# RS485.net
KiCad netlist of a schematic drawn in Altium Designer
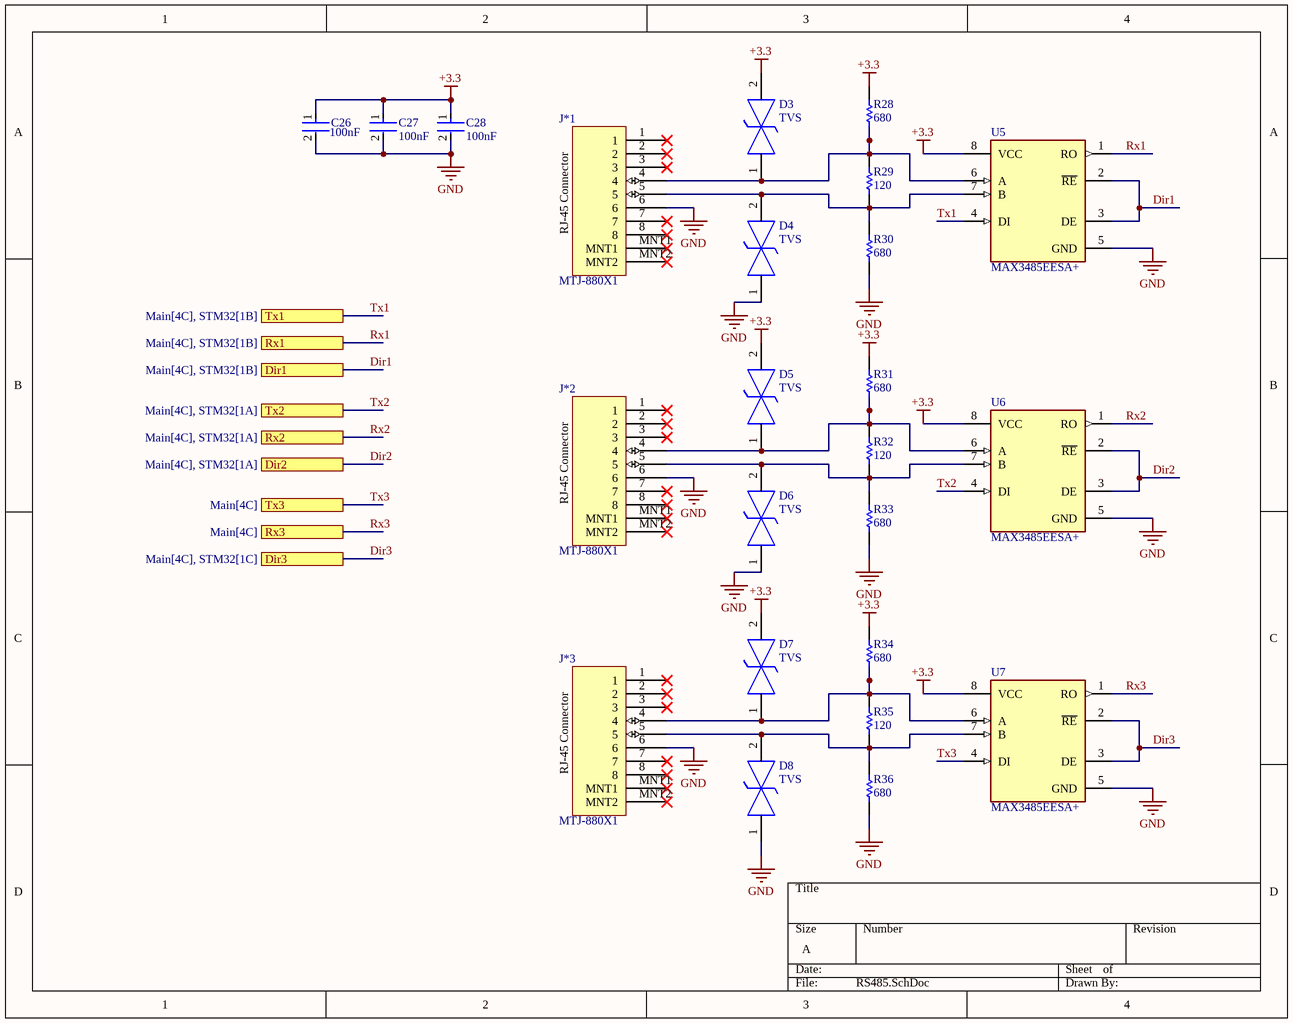
[diagram p0: RS485.SchDoc]

(export (version "E")
  (design (tool "Eeschema 10.0.6"))
  (components
    (comp (ref "C26")
      (value "100nF")
      (footprint "FP-0805-L_2_01_0_2-W_1_25-IPC_B")
      (description "General Purpose Ceramic Capacitor, 0805, 100nF, 10%, X7R, 15%, 100V")
      (fields (field (name "VOLTAGE") "100V") (field (name "TOLERANCE") "10%"))
      (libsource (lib "Altium Content Vault") (part "b4654b650e69147ec39a6b967a45e02"))
    )
    (comp (ref "C27")
      (value "100nF")
      (footprint "FP-0805-L_2_01_0_2-W_1_25-IPC_B")
      (description "General Purpose Ceramic Capacitor, 0805, 100nF, 10%, X7R, 15%, 100V")
      (fields (field (name "VOLTAGE") "100V") (field (name "TOLERANCE") "10%"))
      (libsource (lib "Altium Content Vault") (part "b4654b650e69147ec39a6b967a45e02"))
    )
    (comp (ref "C28")
      (value "100nF")
      (footprint "FP-0805-L_2_01_0_2-W_1_25-IPC_B")
      (description "General Purpose Ceramic Capacitor, 0805, 100nF, 10%, X7R, 15%, 100V")
      (fields (field (name "VOLTAGE") "100V") (field (name "TOLERANCE") "10%"))
      (libsource (lib "Altium Content Vault") (part "b4654b650e69147ec39a6b967a45e02"))
    )
    (comp (ref "D3")
      (value "TVS")
      (footprint "FP-SMB-MFG")
      (description "TVS DIODE 28.2V 59V SMB")
      (fields
        (field (name "OCTOPART") "https://octopart.com/sm6t33ca-stmicroelectronics-55399331")
        (field (name "MANUFACTURER PART NUMBER") "SM6T33CA")
      )
      (libsource (lib "Altium Content Vault") (part "ebc102d6f37e12f28676a717a4d7ff6"))
    )
    (comp (ref "D4")
      (value "TVS")
      (footprint "FP-SMB-MFG")
      (description "TVS DIODE 28.2V 59V SMB")
      (fields
        (field (name "OCTOPART") "https://octopart.com/sm6t33ca-stmicroelectronics-55399331")
        (field (name "MANUFACTURER PART NUMBER") "SM6T33CA")
      )
      (libsource (lib "Altium Content Vault") (part "ebc102d6f37e12f28676a717a4d7ff6"))
    )
    (comp (ref "D5")
      (value "TVS")
      (footprint "FP-SMB-MFG")
      (description "TVS DIODE 28.2V 59V SMB")
      (fields
        (field (name "OCTOPART") "https://octopart.com/sm6t33ca-stmicroelectronics-55399331")
        (field (name "MANUFACTURER PART NUMBER") "SM6T33CA")
      )
      (libsource (lib "Altium Content Vault") (part "ebc102d6f37e12f28676a717a4d7ff6"))
    )
    (comp (ref "D6")
      (value "TVS")
      (footprint "FP-SMB-MFG")
      (description "TVS DIODE 28.2V 59V SMB")
      (fields
        (field (name "OCTOPART") "https://octopart.com/sm6t33ca-stmicroelectronics-55399331")
        (field (name "MANUFACTURER PART NUMBER") "SM6T33CA")
      )
      (libsource (lib "Altium Content Vault") (part "ebc102d6f37e12f28676a717a4d7ff6"))
    )
    (comp (ref "D7")
      (value "TVS")
      (footprint "FP-SMB-MFG")
      (description "TVS DIODE 28.2V 59V SMB")
      (fields
        (field (name "OCTOPART") "https://octopart.com/sm6t33ca-stmicroelectronics-55399331")
        (field (name "MANUFACTURER PART NUMBER") "SM6T33CA")
      )
      (libsource (lib "Altium Content Vault") (part "ebc102d6f37e12f28676a717a4d7ff6"))
    )
    (comp (ref "D8")
      (value "TVS")
      (footprint "FP-SMB-MFG")
      (description "TVS DIODE 28.2V 59V SMB")
      (fields
        (field (name "OCTOPART") "https://octopart.com/sm6t33ca-stmicroelectronics-55399331")
        (field (name "MANUFACTURER PART NUMBER") "SM6T33CA")
      )
      (libsource (lib "Altium Content Vault") (part "ebc102d6f37e12f28676a717a4d7ff6"))
    )
    (comp (ref "J*1")
      (value "MTJ-880X1")
      (footprint "MTJ-880X1")
      (libsource (lib "Schematic_library") (part "MTJ-880X1"))
    )
    (comp (ref "J*2")
      (value "MTJ-880X1")
      (footprint "MTJ-880X1")
      (libsource (lib "Schematic_library") (part "MTJ-880X1"))
    )
    (comp (ref "J*3")
      (value "MTJ-880X1")
      (footprint "MTJ-880X1")
      (libsource (lib "Schematic_library") (part "MTJ-880X1"))
    )
    (comp (ref "R28")
      (value "680")
      (footprint "RESC2013X50X30LL20T20")
      (fields (field (name "MANUFACTURER") "Vishay Dale") (field (name "PART NUMBER") "CRCW08050000Z0EA"))
      (libsource (lib "Altium Content Vault") (part "RES"))
    )
    (comp (ref "R29")
      (value "120")
      (footprint "RESC2013X50X30LL20T20")
      (fields (field (name "MANUFACTURER") "Vishay Dale") (field (name "PART NUMBER") "CRCW08050000Z0EA"))
      (libsource (lib "Altium Content Vault") (part "RES"))
    )
    (comp (ref "R30")
      (value "680")
      (footprint "RESC2013X50X30LL20T20")
      (fields (field (name "MANUFACTURER") "Vishay Dale") (field (name "PART NUMBER") "CRCW08050000Z0EA"))
      (libsource (lib "Altium Content Vault") (part "RES"))
    )
    (comp (ref "R31")
      (value "680")
      (footprint "RESC2013X50X30LL20T20")
      (fields (field (name "MANUFACTURER") "Vishay Dale") (field (name "PART NUMBER") "CRCW08050000Z0EA"))
      (libsource (lib "Altium Content Vault") (part "RES"))
    )
    (comp (ref "R32")
      (value "120")
      (footprint "RESC2013X50X30LL20T20")
      (fields (field (name "MANUFACTURER") "Vishay Dale") (field (name "PART NUMBER") "CRCW08050000Z0EA"))
      (libsource (lib "Altium Content Vault") (part "RES"))
    )
    (comp (ref "R33")
      (value "680")
      (footprint "RESC2013X50X30LL20T20")
      (fields (field (name "MANUFACTURER") "Vishay Dale") (field (name "PART NUMBER") "CRCW08050000Z0EA"))
      (libsource (lib "Altium Content Vault") (part "RES"))
    )
    (comp (ref "R34")
      (value "680")
      (footprint "RESC2013X50X30LL20T20")
      (fields (field (name "MANUFACTURER") "Vishay Dale") (field (name "PART NUMBER") "CRCW08050000Z0EA"))
      (libsource (lib "Altium Content Vault") (part "RES"))
    )
    (comp (ref "R35")
      (value "120")
      (footprint "RESC2013X50X30LL20T20")
      (fields (field (name "MANUFACTURER") "Vishay Dale") (field (name "PART NUMBER") "CRCW08050000Z0EA"))
      (libsource (lib "Altium Content Vault") (part "RES"))
    )
    (comp (ref "R36")
      (value "680")
      (footprint "RESC2013X50X30LL20T20")
      (fields (field (name "MANUFACTURER") "Vishay Dale") (field (name "PART NUMBER") "CRCW08050000Z0EA"))
      (libsource (lib "Altium Content Vault") (part "RES"))
    )
    (comp (ref "U5")
      (value "MAX3485EESA+")
      (footprint "FP-S8-5-MFG")
      (description "IC TXRX RS485/422 10MBPS 8SOIC")
      (fields
        (field (name "OCTOPART") "https://octopart.com/max3485eesa%2B-maxim+integrated-39731903")
        (field (name "MANUFACTURER") "Maxim Integrated")
      )
      (libsource (lib "Altium Content Vault") (part "be0caabdb159a9a12bcb36ec340889e"))
    )
    (comp (ref "U6")
      (value "MAX3485EESA+")
      (footprint "FP-S8-5-MFG")
      (description "IC TXRX RS485/422 10MBPS 8SOIC")
      (fields
        (field (name "OCTOPART") "https://octopart.com/max3485eesa%2B-maxim+integrated-39731903")
        (field (name "MANUFACTURER") "Maxim Integrated")
      )
      (libsource (lib "Altium Content Vault") (part "be0caabdb159a9a12bcb36ec340889e"))
    )
    (comp (ref "U7")
      (value "MAX3485EESA+")
      (footprint "FP-S8-5-MFG")
      (description "IC TXRX RS485/422 10MBPS 8SOIC")
      (fields
        (field (name "OCTOPART") "https://octopart.com/max3485eesa%2B-maxim+integrated-39731903")
        (field (name "MANUFACTURER") "Maxim Integrated")
      )
      (libsource (lib "Altium Content Vault") (part "be0caabdb159a9a12bcb36ec340889e"))
    )
  )
  (nets
    (net (code "1") (name "+3.3") (class "Default")
      (node (ref "C26") (pin "1") (pinfunction "1_1") (pintype "passive"))
      (node (ref "C27") (pin "1") (pinfunction "1_1") (pintype "passive"))
      (node (ref "C28") (pin "1") (pinfunction "1_1") (pintype "passive"))
      (node (ref "D3") (pin "2") (pinfunction "2_2") (pintype "passive"))
      (node (ref "D5") (pin "2") (pinfunction "2_2") (pintype "passive"))
      (node (ref "D7") (pin "2") (pinfunction "2_2") (pintype "passive"))
      (node (ref "R28") (pin "2") (pinfunction "2_2") (pintype "passive"))
      (node (ref "R31") (pin "2") (pinfunction "2_2") (pintype "passive"))
      (node (ref "R34") (pin "2") (pinfunction "2_2") (pintype "passive"))
      (node (ref "U5") (pin "8") (pinfunction "VCC_8") (pintype "power_in"))
      (node (ref "U6") (pin "8") (pinfunction "VCC_8") (pintype "power_in"))
      (node (ref "U7") (pin "8") (pinfunction "VCC_8") (pintype "power_in"))
    )
    (net (code "2") (name "/Dir1") (class "Default")
      (node (ref "U5") (pin "2") (pinfunction "~{RE}_2") (pintype "passive"))
      (node (ref "U5") (pin "3") (pinfunction "DE_3") (pintype "passive"))
    )
    (net (code "3") (name "/Dir2") (class "Default")
      (node (ref "U6") (pin "2") (pinfunction "~{RE}_2") (pintype "passive"))
      (node (ref "U6") (pin "3") (pinfunction "DE_3") (pintype "passive"))
    )
    (net (code "4") (name "/Dir3") (class "Default")
      (node (ref "U7") (pin "2") (pinfunction "~{RE}_2") (pintype "passive"))
      (node (ref "U7") (pin "3") (pinfunction "DE_3") (pintype "passive"))
    )
    (net (code "5") (name "/Rx1") (class "Default")
      (node (ref "U5") (pin "1") (pinfunction "RO_1") (pintype "output"))
    )
    (net (code "6") (name "/Rx2") (class "Default")
      (node (ref "U6") (pin "1") (pinfunction "RO_1") (pintype "output"))
    )
    (net (code "7") (name "/Rx3") (class "Default")
      (node (ref "U7") (pin "1") (pinfunction "RO_1") (pintype "output"))
    )
    (net (code "8") (name "/Tx1") (class "Default")
      (node (ref "U5") (pin "4") (pinfunction "DI_4") (pintype "input"))
    )
    (net (code "9") (name "/Tx2") (class "Default")
      (node (ref "U6") (pin "4") (pinfunction "DI_4") (pintype "input"))
    )
    (net (code "10") (name "/Tx3") (class "Default")
      (node (ref "U7") (pin "4") (pinfunction "DI_4") (pintype "input"))
    )
    (net (code "11") (name "GND") (class "Default")
      (node (ref "C26") (pin "2") (pinfunction "2_2") (pintype "passive"))
      (node (ref "C27") (pin "2") (pinfunction "2_2") (pintype "passive"))
      (node (ref "C28") (pin "2") (pinfunction "2_2") (pintype "passive"))
      (node (ref "D4") (pin "1") (pinfunction "1_1") (pintype "passive"))
      (node (ref "D6") (pin "1") (pinfunction "1_1") (pintype "passive"))
      (node (ref "D8") (pin "1") (pinfunction "1_1") (pintype "passive"))
      (node (ref "J*1") (pin "6") (pinfunction "6_6") (pintype "passive"))
      (node (ref "J*2") (pin "6") (pinfunction "6_6") (pintype "passive"))
      (node (ref "J*3") (pin "6") (pinfunction "6_6") (pintype "passive"))
      (node (ref "R30") (pin "1") (pinfunction "1_1") (pintype "passive"))
      (node (ref "R33") (pin "1") (pinfunction "1_1") (pintype "passive"))
      (node (ref "R36") (pin "1") (pinfunction "1_1") (pintype "passive"))
      (node (ref "U5") (pin "5") (pinfunction "GND_5") (pintype "power_in"))
      (node (ref "U6") (pin "5") (pinfunction "GND_5") (pintype "power_in"))
      (node (ref "U7") (pin "5") (pinfunction "GND_5") (pintype "power_in"))
    )
    (net (code "12") (name "Net-(U5-A)") (class "Default")
      (node (ref "D3") (pin "1") (pinfunction "1_1") (pintype "passive"))
      (node (ref "J*1") (pin "4") (pinfunction "4_4") (pintype "bidirectional"))
      (node (ref "R28") (pin "1") (pinfunction "1_1") (pintype "passive"))
      (node (ref "R29") (pin "2") (pinfunction "2_2") (pintype "passive"))
      (node (ref "U5") (pin "6") (pinfunction "A_6") (pintype "input"))
    )
    (net (code "13") (name "Net-(U5-B)") (class "Default")
      (node (ref "D4") (pin "2") (pinfunction "2_2") (pintype "passive"))
      (node (ref "J*1") (pin "5") (pinfunction "5_5") (pintype "bidirectional"))
      (node (ref "R29") (pin "1") (pinfunction "1_1") (pintype "passive"))
      (node (ref "R30") (pin "2") (pinfunction "2_2") (pintype "passive"))
      (node (ref "U5") (pin "7") (pinfunction "B_7") (pintype "input"))
    )
    (net (code "14") (name "Net-(U6-A)") (class "Default")
      (node (ref "D5") (pin "1") (pinfunction "1_1") (pintype "passive"))
      (node (ref "J*2") (pin "4") (pinfunction "4_4") (pintype "bidirectional"))
      (node (ref "R31") (pin "1") (pinfunction "1_1") (pintype "passive"))
      (node (ref "R32") (pin "2") (pinfunction "2_2") (pintype "passive"))
      (node (ref "U6") (pin "6") (pinfunction "A_6") (pintype "input"))
    )
    (net (code "15") (name "Net-(U6-B)") (class "Default")
      (node (ref "D6") (pin "2") (pinfunction "2_2") (pintype "passive"))
      (node (ref "J*2") (pin "5") (pinfunction "5_5") (pintype "bidirectional"))
      (node (ref "R32") (pin "1") (pinfunction "1_1") (pintype "passive"))
      (node (ref "R33") (pin "2") (pinfunction "2_2") (pintype "passive"))
      (node (ref "U6") (pin "7") (pinfunction "B_7") (pintype "input"))
    )
    (net (code "16") (name "Net-(U7-A)") (class "Default")
      (node (ref "D7") (pin "1") (pinfunction "1_1") (pintype "passive"))
      (node (ref "J*3") (pin "4") (pinfunction "4_4") (pintype "bidirectional"))
      (node (ref "R34") (pin "1") (pinfunction "1_1") (pintype "passive"))
      (node (ref "R35") (pin "2") (pinfunction "2_2") (pintype "passive"))
      (node (ref "U7") (pin "6") (pinfunction "A_6") (pintype "input"))
    )
    (net (code "17") (name "Net-(U7-B)") (class "Default")
      (node (ref "D8") (pin "2") (pinfunction "2_2") (pintype "passive"))
      (node (ref "J*3") (pin "5") (pinfunction "5_5") (pintype "bidirectional"))
      (node (ref "R35") (pin "1") (pinfunction "1_1") (pintype "passive"))
      (node (ref "R36") (pin "2") (pinfunction "2_2") (pintype "passive"))
      (node (ref "U7") (pin "7") (pinfunction "B_7") (pintype "input"))
    )
    (net (code "18") (name "unconnected-(J*1-Pad1)") (class "Default")
      (node (ref "J*1") (pin "1") (pinfunction "1_1") (pintype "passive+no_connect"))
    )
    (net (code "19") (name "unconnected-(J*1-Pad2)") (class "Default")
      (node (ref "J*1") (pin "2") (pinfunction "2_2") (pintype "passive+no_connect"))
    )
    (net (code "20") (name "unconnected-(J*1-Pad3)") (class "Default")
      (node (ref "J*1") (pin "3") (pinfunction "3_3") (pintype "passive+no_connect"))
    )
    (net (code "21") (name "unconnected-(J*1-Pad7)") (class "Default")
      (node (ref "J*1") (pin "7") (pinfunction "7_7") (pintype "passive+no_connect"))
    )
    (net (code "22") (name "unconnected-(J*1-Pad8)") (class "Default")
      (node (ref "J*1") (pin "8") (pinfunction "8_8") (pintype "passive+no_connect"))
    )
    (net (code "23") (name "unconnected-(J*1-PadMNT1)") (class "Default")
      (node (ref "J*1") (pin "MNT1") (pinfunction "MNT1_MNT1") (pintype "passive+no_connect"))
    )
    (net (code "24") (name "unconnected-(J*1-PadMNT2)") (class "Default")
      (node (ref "J*1") (pin "MNT2") (pinfunction "MNT2_MNT2") (pintype "passive+no_connect"))
    )
    (net (code "25") (name "unconnected-(J*2-Pad1)") (class "Default")
      (node (ref "J*2") (pin "1") (pinfunction "1_1") (pintype "passive+no_connect"))
    )
    (net (code "26") (name "unconnected-(J*2-Pad2)") (class "Default")
      (node (ref "J*2") (pin "2") (pinfunction "2_2") (pintype "passive+no_connect"))
    )
    (net (code "27") (name "unconnected-(J*2-Pad3)") (class "Default")
      (node (ref "J*2") (pin "3") (pinfunction "3_3") (pintype "passive+no_connect"))
    )
    (net (code "28") (name "unconnected-(J*2-Pad7)") (class "Default")
      (node (ref "J*2") (pin "7") (pinfunction "7_7") (pintype "passive+no_connect"))
    )
    (net (code "29") (name "unconnected-(J*2-Pad8)") (class "Default")
      (node (ref "J*2") (pin "8") (pinfunction "8_8") (pintype "passive+no_connect"))
    )
    (net (code "30") (name "unconnected-(J*2-PadMNT1)") (class "Default")
      (node (ref "J*2") (pin "MNT1") (pinfunction "MNT1_MNT1") (pintype "passive+no_connect"))
    )
    (net (code "31") (name "unconnected-(J*2-PadMNT2)") (class "Default")
      (node (ref "J*2") (pin "MNT2") (pinfunction "MNT2_MNT2") (pintype "passive+no_connect"))
    )
    (net (code "32") (name "unconnected-(J*3-Pad1)") (class "Default")
      (node (ref "J*3") (pin "1") (pinfunction "1_1") (pintype "passive+no_connect"))
    )
    (net (code "33") (name "unconnected-(J*3-Pad2)") (class "Default")
      (node (ref "J*3") (pin "2") (pinfunction "2_2") (pintype "passive+no_connect"))
    )
    (net (code "34") (name "unconnected-(J*3-Pad3)") (class "Default")
      (node (ref "J*3") (pin "3") (pinfunction "3_3") (pintype "passive+no_connect"))
    )
    (net (code "35") (name "unconnected-(J*3-Pad7)") (class "Default")
      (node (ref "J*3") (pin "7") (pinfunction "7_7") (pintype "passive+no_connect"))
    )
    (net (code "36") (name "unconnected-(J*3-Pad8)") (class "Default")
      (node (ref "J*3") (pin "8") (pinfunction "8_8") (pintype "passive+no_connect"))
    )
    (net (code "37") (name "unconnected-(J*3-PadMNT1)") (class "Default")
      (node (ref "J*3") (pin "MNT1") (pinfunction "MNT1_MNT1") (pintype "passive+no_connect"))
    )
    (net (code "38") (name "unconnected-(J*3-PadMNT2)") (class "Default")
      (node (ref "J*3") (pin "MNT2") (pinfunction "MNT2_MNT2") (pintype "passive+no_connect"))
    )
  )
)
